# monostable.net
KiCad netlist of a schematic drawn in EAGLE
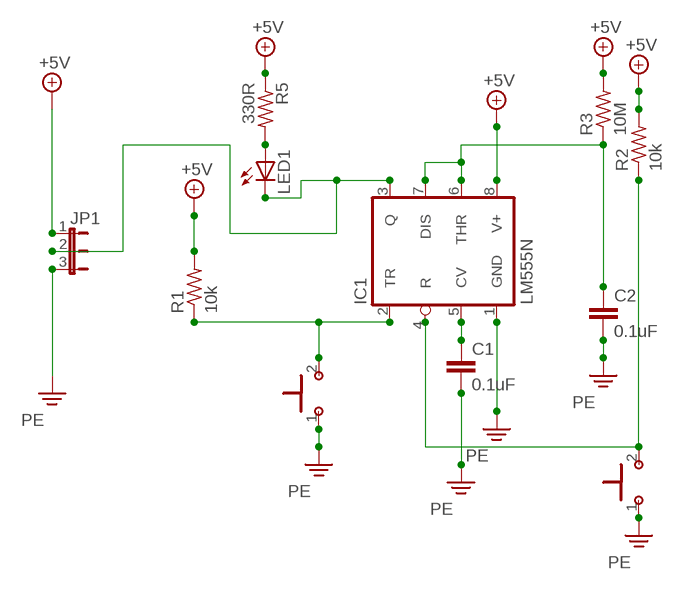
[diagram p0: schematic, sheet 1]

(export (version "E")
  (design (tool "Eeschema 10.0.6"))
  (components
    (comp (ref "C1")
      (value "0.1uF")
      (footprint "eagle-import:C075-032X103")
      (libsource (lib "eagle-import") (part "C-EU075-032X103"))
    )
    (comp (ref "C2")
      (value "0.1uF")
      (footprint "eagle-import:C075-032X103")
      (libsource (lib "eagle-import") (part "C-EU075-032X103"))
    )
    (comp (ref "IC1")
      (value "LM555N")
      (footprint "eagle-import:DIL08")
      (libsource (lib "eagle-import") (part "555NLM"))
    )
    (comp (ref "JP1")
      (value "JP2E")
      (footprint "eagle-import:JP2")
      (libsource (lib "eagle-import") (part "JP2E"))
    )
    (comp (ref "LED1")
      (value "LED5MM")
      (footprint "eagle-import:LED5MM")
      (libsource (lib "eagle-import") (part "LED5MM"))
    )
    (comp (ref "R1")
      (value "10k")
      (footprint "eagle-import:0207_10")
      (libsource (lib "eagle-import") (part "R-US_0207/10"))
    )
    (comp (ref "R2")
      (value "10k")
      (footprint "eagle-import:0207_10")
      (libsource (lib "eagle-import") (part "R-US_0207/10"))
    )
    (comp (ref "R3")
      (value "10M")
      (footprint "eagle-import:0207_10")
      (libsource (lib "eagle-import") (part "R-US_0207/10"))
    )
    (comp (ref "R5")
      (value "330R")
      (footprint "eagle-import:0207_10")
      (libsource (lib "eagle-import") (part "R-US_0207/10"))
    )
    (comp (ref "U$1")
      (value "PUSHBUTTON")
      (footprint "eagle-import:PUSHBUTTON")
      (libsource (lib "eagle-import") (part "PUSHBUTTON"))
    )
    (comp (ref "U$2")
      (value "PUSHBUTTON")
      (footprint "eagle-import:PUSHBUTTON")
      (libsource (lib "eagle-import") (part "PUSHBUTTON"))
    )
  )
  (nets
    (net (code "1") (name "+5V") (class "Default")
      (node (ref "IC1") (pin "8") (pinfunction "V+_8") (pintype "power_in"))
      (node (ref "JP1") (pin "1") (pinfunction "1_1") (pintype "passive"))
      (node (ref "R1") (pin "2") (pinfunction "2_2") (pintype "passive"))
      (node (ref "R2") (pin "2") (pinfunction "2_2") (pintype "passive"))
      (node (ref "R3") (pin "2") (pinfunction "2_2") (pintype "passive"))
      (node (ref "R5") (pin "1") (pinfunction "1_1") (pintype "passive"))
    )
    (net (code "2") (name "Net-(IC1-CV)") (class "Default")
      (node (ref "C1") (pin "1") (pinfunction "1_1") (pintype "passive"))
      (node (ref "IC1") (pin "5") (pinfunction "CV_5") (pintype "input"))
    )
    (net (code "3") (name "Net-(IC1-DIS)") (class "Default")
      (node (ref "C2") (pin "1") (pinfunction "1_1") (pintype "passive"))
      (node (ref "IC1") (pin "6") (pinfunction "THR_6") (pintype "input"))
      (node (ref "IC1") (pin "7") (pinfunction "DIS_7") (pintype "input"))
      (node (ref "R3") (pin "1") (pinfunction "1_1") (pintype "passive"))
    )
    (net (code "4") (name "Net-(IC1-Q)") (class "Default")
      (node (ref "IC1") (pin "3") (pinfunction "Q_3") (pintype "output"))
      (node (ref "JP1") (pin "2") (pinfunction "2_2") (pintype "passive"))
      (node (ref "LED1") (pin "K") (pinfunction "C_K") (pintype "passive"))
    )
    (net (code "5") (name "Net-(IC1-R)") (class "Default")
      (node (ref "IC1") (pin "4") (pinfunction "R_4") (pintype "input"))
      (node (ref "R2") (pin "1") (pinfunction "1_1") (pintype "passive"))
      (node (ref "U$2") (pin "2") (pinfunction "2_2") (pintype "bidirectional"))
    )
    (net (code "6") (name "Net-(IC1-TR)") (class "Default")
      (node (ref "IC1") (pin "2") (pinfunction "TR_2") (pintype "input"))
      (node (ref "R1") (pin "1") (pinfunction "1_1") (pintype "passive"))
      (node (ref "U$1") (pin "2") (pinfunction "2_2") (pintype "bidirectional"))
    )
    (net (code "7") (name "Net-(LED1-PadA)") (class "Default")
      (node (ref "LED1") (pin "A") (pinfunction "A_A") (pintype "passive"))
      (node (ref "R5") (pin "2") (pinfunction "2_2") (pintype "passive"))
    )
    (net (code "8") (name "PE") (class "Default")
      (node (ref "C1") (pin "2") (pinfunction "2_2") (pintype "passive"))
      (node (ref "C2") (pin "2") (pinfunction "2_2") (pintype "passive"))
      (node (ref "IC1") (pin "1") (pinfunction "GND_1") (pintype "power_in"))
      (node (ref "JP1") (pin "3") (pinfunction "3_3") (pintype "passive"))
      (node (ref "U$1") (pin "1") (pinfunction "1_1") (pintype "bidirectional"))
      (node (ref "U$2") (pin "1") (pinfunction "1_1") (pintype "bidirectional"))
    )
  )
)
